# Memory_Board.net
KiCad netlist of a schematic drawn in EAGLE
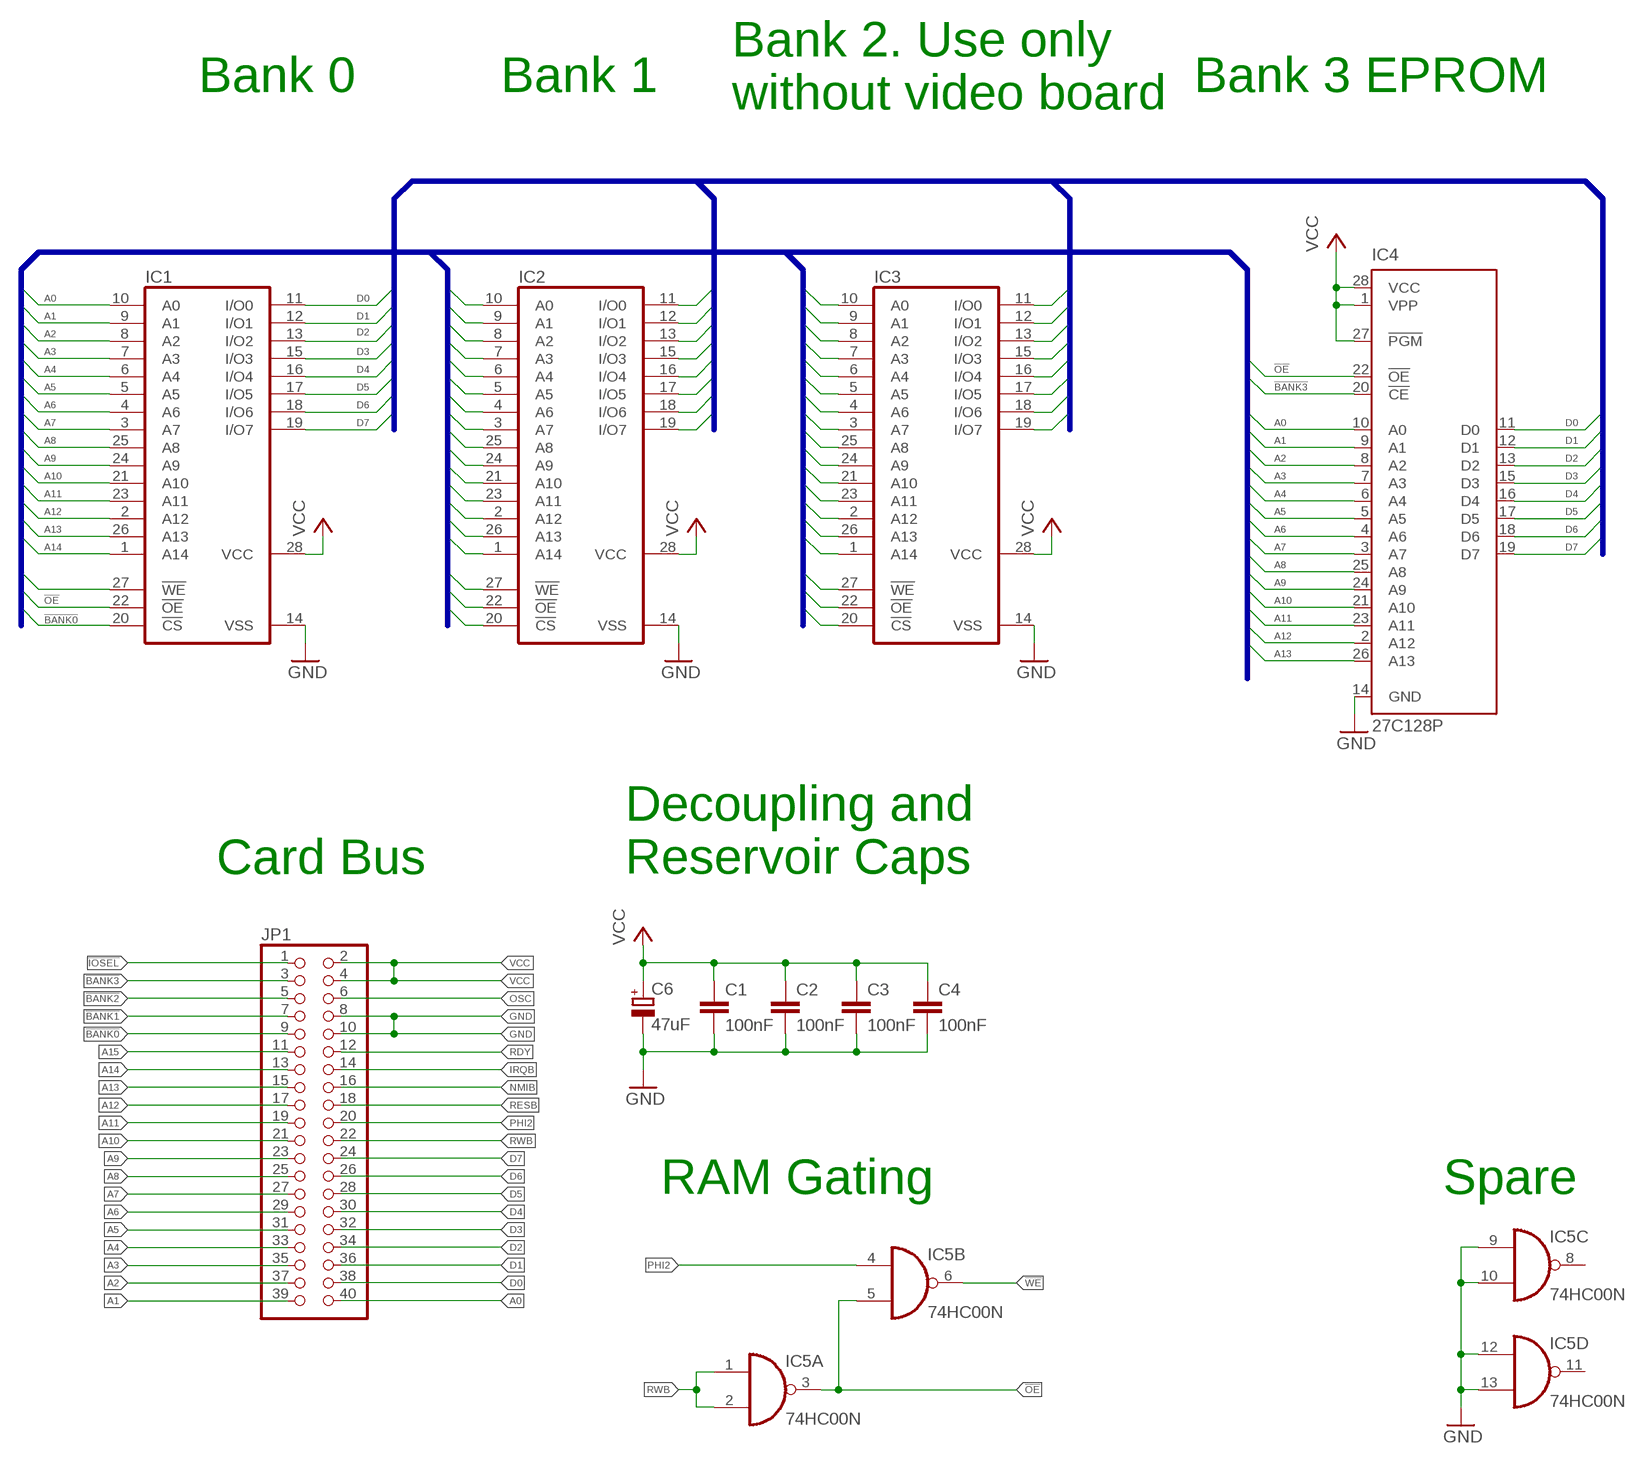
[diagram p0: schematic, sheet 1]

(export (version "E")
  (design (tool "Eeschema 10.0.6"))
  (components
    (comp (ref "C1")
      (value "100nF")
      (footprint "eagle-import:C050-025X075")
      (libsource (lib "eagle-import") (part "C-EU050-025X075"))
    )
    (comp (ref "C2")
      (value "100nF")
      (footprint "eagle-import:C050-025X075")
      (libsource (lib "eagle-import") (part "C-EU050-025X075"))
    )
    (comp (ref "C3")
      (value "100nF")
      (footprint "eagle-import:C050-025X075")
      (libsource (lib "eagle-import") (part "C-EU050-025X075"))
    )
    (comp (ref "C4")
      (value "100nF")
      (footprint "eagle-import:C050-025X075")
      (libsource (lib "eagle-import") (part "C-EU050-025X075"))
    )
    (comp (ref "C6")
      (value "47uF")
      (footprint "eagle-import:E2,5-7")
      (libsource (lib "eagle-import") (part "CPOL-EUE2.5-7"))
    )
    (comp (ref "IC1")
      (value "62256P")
      (footprint "eagle-import:DIL28-6")
      (libsource (lib "eagle-import") (part "62256P"))
    )
    (comp (ref "IC2")
      (value "62256P")
      (footprint "eagle-import:DIL28-6")
      (libsource (lib "eagle-import") (part "62256P"))
    )
    (comp (ref "IC3")
      (value "62256P")
      (footprint "eagle-import:DIL28-6")
      (libsource (lib "eagle-import") (part "62256P"))
    )
    (comp (ref "IC4")
      (value "27C128P")
      (footprint "eagle-import:DIL28-6")
      (libsource (lib "eagle-import") (part "27128PC"))
    )
    (comp (ref "IC5")
      (value "74HC00N")
      (footprint "eagle-import:DIL14")
      (libsource (lib "eagle-import") (part "7400NHC"))
    )
    (comp (ref "JP1")
      (value "PINHD-2X20/90")
      (footprint "eagle-import:2X20_90")
      (libsource (lib "eagle-import") (part "PINHD-2X20/90"))
    )
  )
  (nets
    (net (code "1") (name "/~{BANK0}") (class "Default")
      (node (ref "IC1") (pin "20") (pinfunction "~{CS}_20") (pintype "input"))
      (node (ref "JP1") (pin "9") (pinfunction "9_9") (pintype "passive"))
    )
    (net (code "2") (name "/~{BANK1}") (class "Default")
      (node (ref "IC2") (pin "20") (pinfunction "~{CS}_20") (pintype "input"))
      (node (ref "JP1") (pin "7") (pinfunction "7_7") (pintype "passive"))
    )
    (net (code "3") (name "/~{BANK2}") (class "Default")
      (node (ref "IC3") (pin "20") (pinfunction "~{CS}_20") (pintype "input"))
      (node (ref "JP1") (pin "5") (pinfunction "5_5") (pintype "passive"))
    )
    (net (code "4") (name "/~{BANK3}") (class "Default")
      (node (ref "IC4") (pin "20") (pinfunction "~{CE}_20") (pintype "input"))
      (node (ref "JP1") (pin "3") (pinfunction "3_3") (pintype "passive"))
    )
    (net (code "5") (name "/~{IOSEL}") (class "Default")
      (node (ref "JP1") (pin "1") (pinfunction "1_1") (pintype "passive"))
    )
    (net (code "6") (name "/~{OE}") (class "Default")
      (node (ref "IC1") (pin "22") (pinfunction "~{OE}_22") (pintype "input"))
      (node (ref "IC2") (pin "22") (pinfunction "~{OE}_22") (pintype "input"))
      (node (ref "IC3") (pin "22") (pinfunction "~{OE}_22") (pintype "input"))
      (node (ref "IC4") (pin "22") (pinfunction "~{OE}_22") (pintype "input"))
      (node (ref "IC5") (pin "3") (pinfunction "O_3") (pintype "output"))
      (node (ref "IC5") (pin "5") (pinfunction "I1_5") (pintype "input"))
    )
    (net (code "7") (name "/~{WE}") (class "Default")
      (node (ref "IC1") (pin "27") (pinfunction "~{WE}_27") (pintype "input"))
      (node (ref "IC2") (pin "27") (pinfunction "~{WE}_27") (pintype "input"))
      (node (ref "IC3") (pin "27") (pinfunction "~{WE}_27") (pintype "input"))
      (node (ref "IC5") (pin "6") (pinfunction "O_6") (pintype "output"))
    )
    (net (code "8") (name "A0") (class "Default")
      (node (ref "IC1") (pin "10") (pinfunction "A0_10") (pintype "input"))
      (node (ref "IC2") (pin "10") (pinfunction "A0_10") (pintype "input"))
      (node (ref "IC3") (pin "10") (pinfunction "A0_10") (pintype "input"))
      (node (ref "IC4") (pin "10") (pinfunction "A0_10") (pintype "input"))
      (node (ref "JP1") (pin "40") (pinfunction "40_40") (pintype "passive"))
    )
    (net (code "9") (name "A1") (class "Default")
      (node (ref "IC1") (pin "9") (pinfunction "A1_9") (pintype "input"))
      (node (ref "IC2") (pin "9") (pinfunction "A1_9") (pintype "input"))
      (node (ref "IC3") (pin "9") (pinfunction "A1_9") (pintype "input"))
      (node (ref "IC4") (pin "9") (pinfunction "A1_9") (pintype "input"))
      (node (ref "JP1") (pin "39") (pinfunction "39_39") (pintype "passive"))
    )
    (net (code "10") (name "A2") (class "Default")
      (node (ref "IC1") (pin "8") (pinfunction "A2_8") (pintype "input"))
      (node (ref "IC2") (pin "8") (pinfunction "A2_8") (pintype "input"))
      (node (ref "IC3") (pin "8") (pinfunction "A2_8") (pintype "input"))
      (node (ref "IC4") (pin "8") (pinfunction "A2_8") (pintype "input"))
      (node (ref "JP1") (pin "37") (pinfunction "37_37") (pintype "passive"))
    )
    (net (code "11") (name "A3") (class "Default")
      (node (ref "IC1") (pin "7") (pinfunction "A3_7") (pintype "input"))
      (node (ref "IC2") (pin "7") (pinfunction "A3_7") (pintype "input"))
      (node (ref "IC3") (pin "7") (pinfunction "A3_7") (pintype "input"))
      (node (ref "IC4") (pin "7") (pinfunction "A3_7") (pintype "input"))
      (node (ref "JP1") (pin "35") (pinfunction "35_35") (pintype "passive"))
    )
    (net (code "12") (name "A4") (class "Default")
      (node (ref "IC1") (pin "6") (pinfunction "A4_6") (pintype "input"))
      (node (ref "IC2") (pin "6") (pinfunction "A4_6") (pintype "input"))
      (node (ref "IC3") (pin "6") (pinfunction "A4_6") (pintype "input"))
      (node (ref "IC4") (pin "6") (pinfunction "A4_6") (pintype "input"))
      (node (ref "JP1") (pin "33") (pinfunction "33_33") (pintype "passive"))
    )
    (net (code "13") (name "A5") (class "Default")
      (node (ref "IC1") (pin "5") (pinfunction "A5_5") (pintype "input"))
      (node (ref "IC2") (pin "5") (pinfunction "A5_5") (pintype "input"))
      (node (ref "IC3") (pin "5") (pinfunction "A5_5") (pintype "input"))
      (node (ref "IC4") (pin "5") (pinfunction "A5_5") (pintype "input"))
      (node (ref "JP1") (pin "31") (pinfunction "31_31") (pintype "passive"))
    )
    (net (code "14") (name "A6") (class "Default")
      (node (ref "IC1") (pin "4") (pinfunction "A6_4") (pintype "input"))
      (node (ref "IC2") (pin "4") (pinfunction "A6_4") (pintype "input"))
      (node (ref "IC3") (pin "4") (pinfunction "A6_4") (pintype "input"))
      (node (ref "IC4") (pin "4") (pinfunction "A6_4") (pintype "input"))
      (node (ref "JP1") (pin "29") (pinfunction "29_29") (pintype "passive"))
    )
    (net (code "15") (name "A7") (class "Default")
      (node (ref "IC1") (pin "3") (pinfunction "A7_3") (pintype "input"))
      (node (ref "IC2") (pin "3") (pinfunction "A7_3") (pintype "input"))
      (node (ref "IC3") (pin "3") (pinfunction "A7_3") (pintype "input"))
      (node (ref "IC4") (pin "3") (pinfunction "A7_3") (pintype "input"))
      (node (ref "JP1") (pin "27") (pinfunction "27_27") (pintype "passive"))
    )
    (net (code "16") (name "A8") (class "Default")
      (node (ref "IC1") (pin "25") (pinfunction "A8_25") (pintype "input"))
      (node (ref "IC2") (pin "25") (pinfunction "A8_25") (pintype "input"))
      (node (ref "IC3") (pin "25") (pinfunction "A8_25") (pintype "input"))
      (node (ref "IC4") (pin "25") (pinfunction "A8_25") (pintype "input"))
      (node (ref "JP1") (pin "25") (pinfunction "25_25") (pintype "passive"))
    )
    (net (code "17") (name "A9") (class "Default")
      (node (ref "IC1") (pin "24") (pinfunction "A9_24") (pintype "input"))
      (node (ref "IC2") (pin "24") (pinfunction "A9_24") (pintype "input"))
      (node (ref "IC3") (pin "24") (pinfunction "A9_24") (pintype "input"))
      (node (ref "IC4") (pin "24") (pinfunction "A9_24") (pintype "input"))
      (node (ref "JP1") (pin "23") (pinfunction "23_23") (pintype "passive"))
    )
    (net (code "18") (name "A10") (class "Default")
      (node (ref "IC1") (pin "21") (pinfunction "A10_21") (pintype "input"))
      (node (ref "IC2") (pin "21") (pinfunction "A10_21") (pintype "input"))
      (node (ref "IC3") (pin "21") (pinfunction "A10_21") (pintype "input"))
      (node (ref "IC4") (pin "21") (pinfunction "A10_21") (pintype "input"))
      (node (ref "JP1") (pin "21") (pinfunction "21_21") (pintype "passive"))
    )
    (net (code "19") (name "A11") (class "Default")
      (node (ref "IC1") (pin "23") (pinfunction "A11_23") (pintype "input"))
      (node (ref "IC2") (pin "23") (pinfunction "A11_23") (pintype "input"))
      (node (ref "IC3") (pin "23") (pinfunction "A11_23") (pintype "input"))
      (node (ref "IC4") (pin "23") (pinfunction "A11_23") (pintype "input"))
      (node (ref "JP1") (pin "19") (pinfunction "19_19") (pintype "passive"))
    )
    (net (code "20") (name "A12") (class "Default")
      (node (ref "IC1") (pin "2") (pinfunction "A12_2") (pintype "input"))
      (node (ref "IC2") (pin "2") (pinfunction "A12_2") (pintype "input"))
      (node (ref "IC3") (pin "2") (pinfunction "A12_2") (pintype "input"))
      (node (ref "IC4") (pin "2") (pinfunction "A12_2") (pintype "input"))
      (node (ref "JP1") (pin "17") (pinfunction "17_17") (pintype "passive"))
    )
    (net (code "21") (name "A13") (class "Default")
      (node (ref "IC1") (pin "26") (pinfunction "A13_26") (pintype "input"))
      (node (ref "IC2") (pin "26") (pinfunction "A13_26") (pintype "input"))
      (node (ref "IC3") (pin "26") (pinfunction "A13_26") (pintype "input"))
      (node (ref "IC4") (pin "26") (pinfunction "A13_26") (pintype "input"))
      (node (ref "JP1") (pin "15") (pinfunction "15_15") (pintype "passive"))
    )
    (net (code "22") (name "A14") (class "Default")
      (node (ref "IC1") (pin "1") (pinfunction "A14_1") (pintype "input"))
      (node (ref "IC2") (pin "1") (pinfunction "A14_1") (pintype "input"))
      (node (ref "IC3") (pin "1") (pinfunction "A14_1") (pintype "input"))
      (node (ref "JP1") (pin "13") (pinfunction "13_13") (pintype "passive"))
    )
    (net (code "23") (name "A15") (class "Default")
      (node (ref "JP1") (pin "11") (pinfunction "11_11") (pintype "passive"))
    )
    (net (code "24") (name "D0") (class "Default")
      (node (ref "IC1") (pin "11") (pinfunction "I/O0_11") (pintype "bidirectional"))
      (node (ref "IC2") (pin "11") (pinfunction "I/O0_11") (pintype "bidirectional"))
      (node (ref "IC3") (pin "11") (pinfunction "I/O0_11") (pintype "bidirectional"))
      (node (ref "IC4") (pin "11") (pinfunction "D0_11") (pintype "tri_state"))
      (node (ref "JP1") (pin "38") (pinfunction "38_38") (pintype "passive"))
    )
    (net (code "25") (name "D1") (class "Default")
      (node (ref "IC1") (pin "12") (pinfunction "I/O1_12") (pintype "bidirectional"))
      (node (ref "IC2") (pin "12") (pinfunction "I/O1_12") (pintype "bidirectional"))
      (node (ref "IC3") (pin "12") (pinfunction "I/O1_12") (pintype "bidirectional"))
      (node (ref "IC4") (pin "12") (pinfunction "D1_12") (pintype "tri_state"))
      (node (ref "JP1") (pin "36") (pinfunction "36_36") (pintype "passive"))
    )
    (net (code "26") (name "D2") (class "Default")
      (node (ref "IC1") (pin "13") (pinfunction "I/O2_13") (pintype "bidirectional"))
      (node (ref "IC2") (pin "13") (pinfunction "I/O2_13") (pintype "bidirectional"))
      (node (ref "IC3") (pin "13") (pinfunction "I/O2_13") (pintype "bidirectional"))
      (node (ref "IC4") (pin "13") (pinfunction "D2_13") (pintype "tri_state"))
      (node (ref "JP1") (pin "34") (pinfunction "34_34") (pintype "passive"))
    )
    (net (code "27") (name "D3") (class "Default")
      (node (ref "IC1") (pin "15") (pinfunction "I/O3_15") (pintype "bidirectional"))
      (node (ref "IC2") (pin "15") (pinfunction "I/O3_15") (pintype "bidirectional"))
      (node (ref "IC3") (pin "15") (pinfunction "I/O3_15") (pintype "bidirectional"))
      (node (ref "IC4") (pin "15") (pinfunction "D3_15") (pintype "tri_state"))
      (node (ref "JP1") (pin "32") (pinfunction "32_32") (pintype "passive"))
    )
    (net (code "28") (name "D4") (class "Default")
      (node (ref "IC1") (pin "16") (pinfunction "I/O4_16") (pintype "bidirectional"))
      (node (ref "IC2") (pin "16") (pinfunction "I/O4_16") (pintype "bidirectional"))
      (node (ref "IC3") (pin "16") (pinfunction "I/O4_16") (pintype "bidirectional"))
      (node (ref "IC4") (pin "16") (pinfunction "D4_16") (pintype "tri_state"))
      (node (ref "JP1") (pin "30") (pinfunction "30_30") (pintype "passive"))
    )
    (net (code "29") (name "D5") (class "Default")
      (node (ref "IC1") (pin "17") (pinfunction "I/O5_17") (pintype "bidirectional"))
      (node (ref "IC2") (pin "17") (pinfunction "I/O5_17") (pintype "bidirectional"))
      (node (ref "IC3") (pin "17") (pinfunction "I/O5_17") (pintype "bidirectional"))
      (node (ref "IC4") (pin "17") (pinfunction "D5_17") (pintype "tri_state"))
      (node (ref "JP1") (pin "28") (pinfunction "28_28") (pintype "passive"))
    )
    (net (code "30") (name "D6") (class "Default")
      (node (ref "IC1") (pin "18") (pinfunction "I/O6_18") (pintype "bidirectional"))
      (node (ref "IC2") (pin "18") (pinfunction "I/O6_18") (pintype "bidirectional"))
      (node (ref "IC3") (pin "18") (pinfunction "I/O6_18") (pintype "bidirectional"))
      (node (ref "IC4") (pin "18") (pinfunction "D6_18") (pintype "tri_state"))
      (node (ref "JP1") (pin "26") (pinfunction "26_26") (pintype "passive"))
    )
    (net (code "31") (name "D7") (class "Default")
      (node (ref "IC1") (pin "19") (pinfunction "I/O7_19") (pintype "bidirectional"))
      (node (ref "IC2") (pin "19") (pinfunction "I/O7_19") (pintype "bidirectional"))
      (node (ref "IC3") (pin "19") (pinfunction "I/O7_19") (pintype "bidirectional"))
      (node (ref "IC4") (pin "19") (pinfunction "D7_19") (pintype "tri_state"))
      (node (ref "JP1") (pin "24") (pinfunction "24_24") (pintype "passive"))
    )
    (net (code "32") (name "GND") (class "Default")
      (node (ref "C1") (pin "2") (pinfunction "2_2") (pintype "passive"))
      (node (ref "C2") (pin "2") (pinfunction "2_2") (pintype "passive"))
      (node (ref "C3") (pin "2") (pinfunction "2_2") (pintype "passive"))
      (node (ref "C4") (pin "2") (pinfunction "2_2") (pintype "passive"))
      (node (ref "C6") (pin "-") (pinfunction "-_-") (pintype "passive"))
      (node (ref "IC1") (pin "14") (pinfunction "VSS_14") (pintype "power_in"))
      (node (ref "IC2") (pin "14") (pinfunction "VSS_14") (pintype "power_in"))
      (node (ref "IC3") (pin "14") (pinfunction "VSS_14") (pintype "power_in"))
      (node (ref "IC4") (pin "14") (pinfunction "GND_14") (pintype "power_in"))
      (node (ref "IC5") (pin "10") (pinfunction "I1_10") (pintype "input"))
      (node (ref "IC5") (pin "12") (pinfunction "I0_12") (pintype "input"))
      (node (ref "IC5") (pin "13") (pinfunction "I1_13") (pintype "input"))
      (node (ref "IC5") (pin "9") (pinfunction "I0_9") (pintype "input"))
      (node (ref "JP1") (pin "10") (pinfunction "10_10") (pintype "passive"))
      (node (ref "JP1") (pin "8") (pinfunction "8_8") (pintype "passive"))
    )
    (net (code "33") (name "IRQB") (class "Default")
      (node (ref "JP1") (pin "14") (pinfunction "14_14") (pintype "passive"))
    )
    (net (code "34") (name "NMIB") (class "Default")
      (node (ref "JP1") (pin "16") (pinfunction "16_16") (pintype "passive"))
    )
    (net (code "35") (name "OSC") (class "Default")
      (node (ref "JP1") (pin "6") (pinfunction "6_6") (pintype "passive"))
    )
    (net (code "36") (name "PHI2") (class "Default")
      (node (ref "IC5") (pin "4") (pinfunction "I0_4") (pintype "input"))
      (node (ref "JP1") (pin "20") (pinfunction "20_20") (pintype "passive"))
    )
    (net (code "37") (name "RDY") (class "Default")
      (node (ref "JP1") (pin "12") (pinfunction "12_12") (pintype "passive"))
    )
    (net (code "38") (name "RESB") (class "Default")
      (node (ref "JP1") (pin "18") (pinfunction "18_18") (pintype "passive"))
    )
    (net (code "39") (name "RWB") (class "Default")
      (node (ref "IC5") (pin "1") (pinfunction "I0_1") (pintype "input"))
      (node (ref "IC5") (pin "2") (pinfunction "I1_2") (pintype "input"))
      (node (ref "JP1") (pin "22") (pinfunction "22_22") (pintype "passive"))
    )
    (net (code "40") (name "VCC") (class "Default")
      (node (ref "C1") (pin "1") (pinfunction "1_1") (pintype "passive"))
      (node (ref "C2") (pin "1") (pinfunction "1_1") (pintype "passive"))
      (node (ref "C3") (pin "1") (pinfunction "1_1") (pintype "passive"))
      (node (ref "C4") (pin "1") (pinfunction "1_1") (pintype "passive"))
      (node (ref "C6") (pin "+") (pinfunction "+_+") (pintype "passive"))
      (node (ref "IC1") (pin "28") (pinfunction "VCC_28") (pintype "power_in"))
      (node (ref "IC2") (pin "28") (pinfunction "VCC_28") (pintype "power_in"))
      (node (ref "IC3") (pin "28") (pinfunction "VCC_28") (pintype "power_in"))
      (node (ref "IC4") (pin "1") (pinfunction "VPP_1") (pintype "input"))
      (node (ref "IC4") (pin "27") (pinfunction "~{PGM}_27") (pintype "passive"))
      (node (ref "IC4") (pin "28") (pinfunction "VCC_28") (pintype "power_in"))
      (node (ref "JP1") (pin "2") (pinfunction "2_2") (pintype "passive"))
      (node (ref "JP1") (pin "4") (pinfunction "4_4") (pintype "passive"))
    )
    (net (code "41") (name "unconnected-(IC5C-O-Pad8)") (class "Default")
      (node (ref "IC5") (pin "8") (pinfunction "O_8") (pintype "output"))
    )
    (net (code "42") (name "unconnected-(IC5D-O-Pad11)") (class "Default")
      (node (ref "IC5") (pin "11") (pinfunction "O_11") (pintype "output"))
    )
  )
)
